# Main.net
KiCad netlist of a schematic drawn in Altium Designer
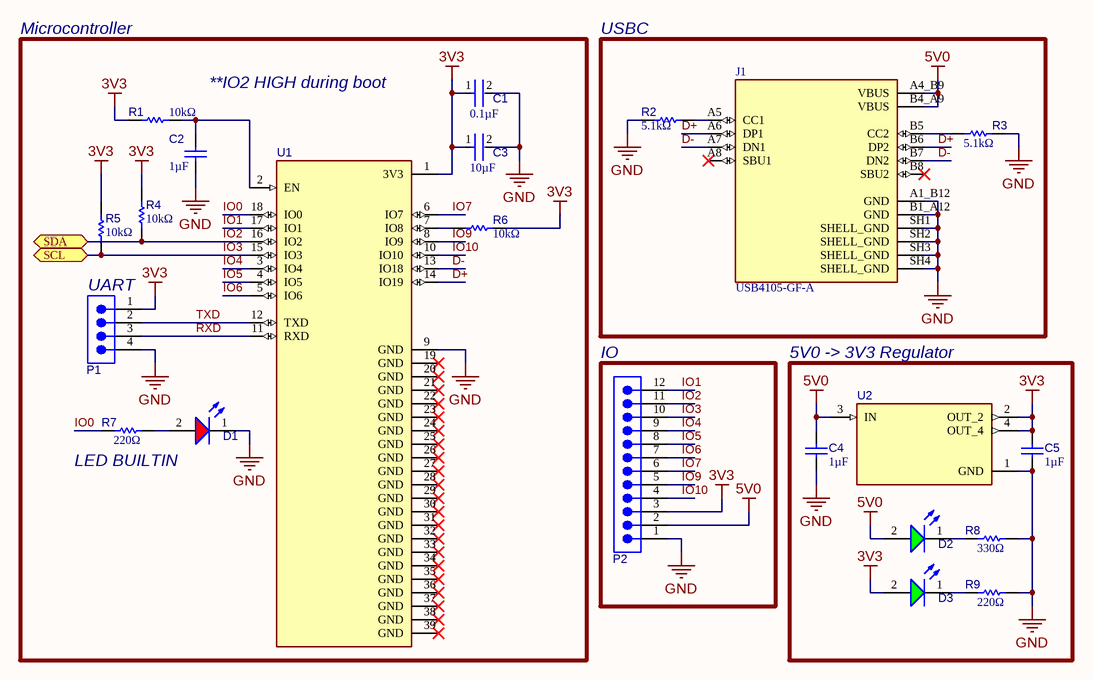
[diagram p0: Main.SchDoc]

(export (version "E")
  (design (tool "Eeschema 10.0.6"))
  (components
    (comp (ref "C1")
      (value "0.1µF")
      (footprint "FP-C1206C-EB-MFG")
      (description "CAP CER 0.1UF 100V X7R 1206")
      (fields
        (field (name "TOLERANCE") "0.1")
        (field (name "OCTOPART") "https://octopart.com/c1206c104k1ractu-kemet-89521")
      )
      (libsource (lib "Altium Content Vault") (part "b4654b650e69147ec39a6b967a45e02"))
    )
    (comp (ref "C2")
      (value "1µF")
      (footprint "CAPC3216X110X50LL20T25")
      (description "Chip Capacitor, 1 uF, +/- 10%, 50 V, -55 to 125 degC, 1206 (3216 Metric), RoHS, Tape and Reel")
      (fields (field (name "MANUFACTURER") "Kemet") (field (name "TOLERANCE") "10%"))
      (libsource (lib "Altium Content Vault") (part "CAP-NP-2"))
    )
    (comp (ref "C3")
      (value "10µF")
      (footprint "FP-GRM31C-0_2-e0_3_0_8-MFG")
      (description "Chip Multilayer Ceramic Capacitors for General Purpose, 1206, 10uF, X7R, 15%, 10%, 25V")
      (fields (field (name "TOLERANCE") "10%") (field (name "VOLTAGE") "25V"))
      (libsource (lib "Altium Content Vault") (part "02cd4be3c70576c341d710602a673aa"))
    )
    (comp (ref "C4")
      (value "1µF")
      (footprint "CAPC3216X110X50LL20T25")
      (description "Chip Capacitor, 1 uF, +/- 10%, 50 V, -55 to 125 degC, 1206 (3216 Metric), RoHS, Tape and Reel")
      (fields (field (name "MANUFACTURER") "Kemet") (field (name "TOLERANCE") "10%"))
      (libsource (lib "Altium Content Vault") (part "CAP-NP-2"))
    )
    (comp (ref "C5")
      (value "1µF")
      (footprint "CAPC3216X110X50LL20T25")
      (description "Chip Capacitor, 1 uF, +/- 10%, 50 V, -55 to 125 degC, 1206 (3216 Metric), RoHS, Tape and Reel")
      (fields (field (name "MANUFACTURER") "Kemet") (field (name "TOLERANCE") "10%"))
      (libsource (lib "Altium Content Vault") (part "CAP-NP-2"))
    )
    (comp (ref "D1")
      (value "150120SS75000")
      (footprint "WL-SMCW_1206_150120xx75000")
      (description "Led, Red, 630 Nm, 1.9 V, 30 Ma, 60 Mcd Rohs Compliant: Yes")
      (libsource (lib "Altium Content Vault") (part "LED_Red_2A-1K"))
    )
    (comp (ref "D2")
      (value "150120GS75000")
      (footprint "WL-SMCW_1206_150120xx75000")
      (description "WL-SMCW SMT Mono-Color Chip LED Waterclear")
      (libsource (lib "Altium Content Vault") (part "LED_Green_2A-1K"))
    )
    (comp (ref "D3")
      (value "150120GS75000")
      (footprint "WL-SMCW_1206_150120xx75000")
      (description "WL-SMCW SMT Mono-Color Chip LED Waterclear")
      (libsource (lib "Altium Content Vault") (part "LED_Green_2A-1K"))
    )
    (comp (ref "J1")
      (value "USB4105-GF-A")
      (footprint "GCT_USB4105-GF-A")
      (fields (field (name "MF") "{'manufacturer': u'GCT'}"))
      (libsource (lib "USB4105-GF-A") (part "USB4105-GF-A"))
    )
    (comp (ref "P1")
      (value "61300411121")
      (footprint "61300411121")
      (description "WR-PHD Pin Header, THT, Vertical, pitch 2.54mm, 1 Row, 4P")
      (fields (field (name "MANUFACTURER") "Wurth Elektronik"))
      (libsource (lib "Altium_WR-PHD_rev24a") (part "61300411121"))
    )
    (comp (ref "P2")
      (value "61301211121")
      (footprint "61301211121")
      (description "WR-PHD Pin Header, THT, Vertical, pitch 2.54mm, 1 Row, 12P")
      (fields (field (name "MANUFACTURER") "Wurth Elektronik"))
      (libsource (lib "Altium_WR-PHD_rev24a") (part "61301211121"))
    )
    (comp (ref "R1")
      (value "10kΩ")
      (footprint "RESC3216X70X50LL20T25")
      (fields (field (name "MANUFACTURER") "Panasonic") (field (name "PART NUMBER") "ERA8AEB103V"))
      (libsource (lib "Altium Content Vault") (part "RES"))
    )
    (comp (ref "R2")
      (value "5.1kΩ")
      (footprint "RESC3216X70X50NL05T20")
      (fields (field (name "PART NUMBER") "ERJ-8ENF5101V") (field (name "MANUFACTURER") "Panasonic"))
      (libsource (lib "Altium Content Vault") (part "RES"))
    )
    (comp (ref "R3")
      (value "5.1kΩ")
      (footprint "RESC3216X70X50NL05T20")
      (fields (field (name "PART NUMBER") "ERJ-8ENF5101V") (field (name "MANUFACTURER") "Panasonic"))
      (libsource (lib "Altium Content Vault") (part "RES"))
    )
    (comp (ref "R4")
      (value "10kΩ")
      (footprint "RESC3216X70X50LL20T25")
      (fields (field (name "MANUFACTURER") "Panasonic") (field (name "PART NUMBER") "ERA8AEB103V"))
      (libsource (lib "Altium Content Vault") (part "RES"))
    )
    (comp (ref "R5")
      (value "10kΩ")
      (footprint "RESC3216X70X50LL20T25")
      (fields (field (name "MANUFACTURER") "Panasonic") (field (name "PART NUMBER") "ERA8AEB103V"))
      (libsource (lib "Altium Content Vault") (part "RES"))
    )
    (comp (ref "R6")
      (value "10kΩ")
      (footprint "RESC3216X70X50LL20T25")
      (fields (field (name "MANUFACTURER") "Panasonic") (field (name "PART NUMBER") "ERA8AEB103V"))
      (libsource (lib "Altium Content Vault") (part "RES"))
    )
    (comp (ref "R7")
      (value "220Ω")
      (footprint "RESC3216X70X50ML20T25")
      (fields (field (name "PART NUMBER") "ERA8AEB221V") (field (name "MANUFACTURER") "Panasonic"))
      (libsource (lib "Altium Content Vault") (part "RES"))
    )
    (comp (ref "R8")
      (value "330Ω")
      (footprint "RESC3216X70X50NL05T20")
      (fields (field (name "MANUFACTURER") "Panasonic") (field (name "PART NUMBER") "ERJ-8GEYJ331V"))
      (libsource (lib "Altium Content Vault") (part "RES"))
    )
    (comp (ref "R9")
      (value "220Ω")
      (footprint "RESC3216X70X50ML20T25")
      (fields (field (name "PART NUMBER") "ERA8AEB221V") (field (name "MANUFACTURER") "Panasonic"))
      (libsource (lib "Altium Content Vault") (part "RES"))
    )
    (comp (ref "U1")
      (value "ESP32-C3-WROOM-02-N4")
      (footprint "MODULE_ESP32-C3-WROOM-02-H4")
      (fields (field (name "MF") "Espressif Systems"))
      (libsource (lib "ESP32-C3-WROOM-02-N4") (part "ESP32-C3-WROOM-02-N4"))
    )
    (comp (ref "U2")
      (value "TLV1117LV33DCYR")
      (footprint "VREG_TLV1117LV33DCYR")
      (description "1-A, low-dropout voltage regulator")
      (fields (field (name "DIGI-KEY_PART_NUMBER") "296-28778-2-ND") (field (name "MF") "Texas Instruments"))
      (libsource (lib "TLV1117LV33DCYR") (part "TLV1117LV33DCYR"))
    )
  )
  (nets
    (net (code "1") (name "/D+") (class "Default")
      (node (ref "J1") (pin "A6") (pinfunction "DP1_A6") (pintype "bidirectional"))
      (node (ref "J1") (pin "B6") (pinfunction "DP2_B6") (pintype "bidirectional"))
      (node (ref "U1") (pin "14") (pinfunction "IO19_14") (pintype "bidirectional"))
    )
    (net (code "2") (name "/D-") (class "Default")
      (node (ref "J1") (pin "A7") (pinfunction "DN1_A7") (pintype "bidirectional"))
      (node (ref "J1") (pin "B7") (pinfunction "DN2_B7") (pintype "bidirectional"))
      (node (ref "U1") (pin "13") (pinfunction "IO18_13") (pintype "bidirectional"))
    )
    (net (code "3") (name "/IO0") (class "Default")
      (node (ref "R7") (pin "1") (pinfunction "1_1") (pintype "passive"))
      (node (ref "U1") (pin "18") (pinfunction "IO0_18") (pintype "bidirectional"))
    )
    (net (code "4") (name "/IO1") (class "Default")
      (node (ref "P2") (pin "12") (pinfunction "12_12") (pintype "passive"))
      (node (ref "U1") (pin "17") (pinfunction "IO1_17") (pintype "bidirectional"))
    )
    (net (code "5") (name "/IO2") (class "Default")
      (node (ref "P2") (pin "11") (pinfunction "11_11") (pintype "passive"))
      (node (ref "R4") (pin "1") (pinfunction "1_1") (pintype "passive"))
      (node (ref "U1") (pin "16") (pinfunction "IO2_16") (pintype "bidirectional"))
    )
    (net (code "6") (name "/IO3") (class "Default")
      (node (ref "P2") (pin "10") (pinfunction "10_10") (pintype "passive"))
      (node (ref "R5") (pin "1") (pinfunction "1_1") (pintype "passive"))
      (node (ref "U1") (pin "15") (pinfunction "IO3_15") (pintype "bidirectional"))
    )
    (net (code "7") (name "/IO4") (class "Default")
      (node (ref "P2") (pin "9") (pinfunction "9_9") (pintype "passive"))
      (node (ref "U1") (pin "3") (pinfunction "IO4_3") (pintype "bidirectional"))
    )
    (net (code "8") (name "/IO5") (class "Default")
      (node (ref "P2") (pin "8") (pinfunction "8_8") (pintype "passive"))
      (node (ref "U1") (pin "4") (pinfunction "IO5_4") (pintype "bidirectional"))
    )
    (net (code "9") (name "/IO6") (class "Default")
      (node (ref "P2") (pin "7") (pinfunction "7_7") (pintype "passive"))
      (node (ref "U1") (pin "5") (pinfunction "IO6_5") (pintype "bidirectional"))
    )
    (net (code "10") (name "/IO7") (class "Default")
      (node (ref "P2") (pin "6") (pinfunction "6_6") (pintype "passive"))
      (node (ref "U1") (pin "6") (pinfunction "IO7_6") (pintype "bidirectional"))
    )
    (net (code "11") (name "/IO9") (class "Default")
      (node (ref "P2") (pin "5") (pinfunction "5_5") (pintype "passive"))
      (node (ref "U1") (pin "8") (pinfunction "IO9_8") (pintype "bidirectional"))
    )
    (net (code "12") (name "/IO10") (class "Default")
      (node (ref "P2") (pin "4") (pinfunction "4_4") (pintype "passive"))
      (node (ref "U1") (pin "10") (pinfunction "IO10_10") (pintype "bidirectional"))
    )
    (net (code "13") (name "/RXD") (class "Default")
      (node (ref "P1") (pin "3") (pinfunction "3_3") (pintype "passive"))
      (node (ref "U1") (pin "11") (pinfunction "RXD_11") (pintype "bidirectional"))
    )
    (net (code "14") (name "/TXD") (class "Default")
      (node (ref "P1") (pin "2") (pinfunction "2_2") (pintype "passive"))
      (node (ref "U1") (pin "12") (pinfunction "TXD_12") (pintype "bidirectional"))
    )
    (net (code "15") (name "3V3") (class "Default")
      (node (ref "C1") (pin "1") (pinfunction "1_1") (pintype "passive"))
      (node (ref "C3") (pin "1") (pinfunction "1_1") (pintype "passive"))
      (node (ref "C5") (pin "2") (pinfunction "2_2") (pintype "passive"))
      (node (ref "D3") (pin "2") (pinfunction "A_2") (pintype "passive"))
      (node (ref "P1") (pin "1") (pinfunction "1_1") (pintype "passive"))
      (node (ref "P2") (pin "3") (pinfunction "3_3") (pintype "passive"))
      (node (ref "R1") (pin "1") (pinfunction "1_1") (pintype "passive"))
      (node (ref "R4") (pin "2") (pinfunction "2_2") (pintype "passive"))
      (node (ref "R5") (pin "2") (pinfunction "2_2") (pintype "passive"))
      (node (ref "R6") (pin "2") (pinfunction "2_2") (pintype "passive"))
      (node (ref "U1") (pin "1") (pinfunction "3V3_1") (pintype "power_in"))
      (node (ref "U2") (pin "2") (pinfunction "OUT_2_2") (pintype "output"))
      (node (ref "U2") (pin "4") (pinfunction "OUT_4_4") (pintype "output"))
    )
    (net (code "16") (name "5V0") (class "Default")
      (node (ref "C4") (pin "2") (pinfunction "2_2") (pintype "passive"))
      (node (ref "D2") (pin "2") (pinfunction "A_2") (pintype "passive"))
      (node (ref "J1") (pin "A4_B9") (pinfunction "VBUS_A4_B9") (pintype "power_in"))
      (node (ref "J1") (pin "B4_A9") (pinfunction "VBUS_B4_A9") (pintype "power_in"))
      (node (ref "P2") (pin "2") (pinfunction "2_2") (pintype "passive"))
      (node (ref "U2") (pin "3") (pinfunction "IN_3") (pintype "input"))
    )
    (net (code "17") (name "GND") (class "Default")
      (node (ref "C1") (pin "2") (pinfunction "2_2") (pintype "passive"))
      (node (ref "C2") (pin "1") (pinfunction "1_1") (pintype "passive"))
      (node (ref "C3") (pin "2") (pinfunction "2_2") (pintype "passive"))
      (node (ref "C4") (pin "1") (pinfunction "1_1") (pintype "passive"))
      (node (ref "C5") (pin "1") (pinfunction "1_1") (pintype "passive"))
      (node (ref "D1") (pin "1") (pinfunction "K_1") (pintype "passive"))
      (node (ref "J1") (pin "A1_B12") (pinfunction "GND_A1_B12") (pintype "power_in"))
      (node (ref "J1") (pin "B1_A12") (pinfunction "GND_B1_A12") (pintype "power_in"))
      (node (ref "J1") (pin "SH1") (pinfunction "SHELL_GND_SH1") (pintype "power_in"))
      (node (ref "J1") (pin "SH2") (pinfunction "SHELL_GND_SH2") (pintype "power_in"))
      (node (ref "J1") (pin "SH3") (pinfunction "SHELL_GND_SH3") (pintype "power_in"))
      (node (ref "J1") (pin "SH4") (pinfunction "SHELL_GND_SH4") (pintype "power_in"))
      (node (ref "P1") (pin "4") (pinfunction "4_4") (pintype "passive"))
      (node (ref "P2") (pin "1") (pinfunction "1_1") (pintype "passive"))
      (node (ref "R2") (pin "1") (pinfunction "1_1") (pintype "passive"))
      (node (ref "R3") (pin "2") (pinfunction "2_2") (pintype "passive"))
      (node (ref "R8") (pin "2") (pinfunction "2_2") (pintype "passive"))
      (node (ref "R9") (pin "2") (pinfunction "2_2") (pintype "passive"))
      (node (ref "U1") (pin "9") (pinfunction "GND_9") (pintype "power_in"))
      (node (ref "U2") (pin "1") (pinfunction "GND_1") (pintype "power_in"))
    )
    (net (code "18") (name "Net-(D1-A)") (class "Default")
      (node (ref "D1") (pin "2") (pinfunction "A_2") (pintype "passive"))
      (node (ref "R7") (pin "2") (pinfunction "2_2") (pintype "passive"))
    )
    (net (code "19") (name "Net-(D2-K)") (class "Default")
      (node (ref "D2") (pin "1") (pinfunction "K_1") (pintype "passive"))
      (node (ref "R8") (pin "1") (pinfunction "1_1") (pintype "passive"))
    )
    (net (code "20") (name "Net-(D3-K)") (class "Default")
      (node (ref "D3") (pin "1") (pinfunction "K_1") (pintype "passive"))
      (node (ref "R9") (pin "1") (pinfunction "1_1") (pintype "passive"))
    )
    (net (code "21") (name "Net-(J1-CC1)") (class "Default")
      (node (ref "J1") (pin "A5") (pinfunction "CC1_A5") (pintype "bidirectional"))
      (node (ref "R2") (pin "2") (pinfunction "2_2") (pintype "passive"))
    )
    (net (code "22") (name "Net-(J1-CC2)") (class "Default")
      (node (ref "J1") (pin "B5") (pinfunction "CC2_B5") (pintype "bidirectional"))
      (node (ref "R3") (pin "1") (pinfunction "1_1") (pintype "passive"))
    )
    (net (code "23") (name "Net-(U1-EN)") (class "Default")
      (node (ref "C2") (pin "2") (pinfunction "2_2") (pintype "passive"))
      (node (ref "R1") (pin "2") (pinfunction "2_2") (pintype "passive"))
      (node (ref "U1") (pin "2") (pinfunction "EN_2") (pintype "input"))
    )
    (net (code "24") (name "Net-(U1-IO8)") (class "Default")
      (node (ref "R6") (pin "1") (pinfunction "1_1") (pintype "passive"))
      (node (ref "U1") (pin "7") (pinfunction "IO8_7") (pintype "bidirectional"))
    )
    (net (code "25") (name "unconnected-(J1-SBU1-PadA8)") (class "Default")
      (node (ref "J1") (pin "A8") (pinfunction "SBU1_A8") (pintype "bidirectional+no_connect"))
    )
    (net (code "26") (name "unconnected-(J1-SBU2-PadB8)") (class "Default")
      (node (ref "J1") (pin "B8") (pinfunction "SBU2_B8") (pintype "bidirectional+no_connect"))
    )
    (net (code "27") (name "unconnected-(U1-GND-Pad19)") (class "Default")
      (node (ref "U1") (pin "19") (pinfunction "GND_19") (pintype "power_in+no_connect"))
    )
    (net (code "28") (name "unconnected-(U1-GND-Pad20)") (class "Default")
      (node (ref "U1") (pin "20") (pinfunction "GND_20") (pintype "power_in+no_connect"))
    )
    (net (code "29") (name "unconnected-(U1-GND-Pad21)") (class "Default")
      (node (ref "U1") (pin "21") (pinfunction "GND_21") (pintype "power_in+no_connect"))
    )
    (net (code "30") (name "unconnected-(U1-GND-Pad22)") (class "Default")
      (node (ref "U1") (pin "22") (pinfunction "GND_22") (pintype "power_in+no_connect"))
    )
    (net (code "31") (name "unconnected-(U1-GND-Pad23)") (class "Default")
      (node (ref "U1") (pin "23") (pinfunction "GND_23") (pintype "power_in+no_connect"))
    )
    (net (code "32") (name "unconnected-(U1-GND-Pad24)") (class "Default")
      (node (ref "U1") (pin "24") (pinfunction "GND_24") (pintype "power_in+no_connect"))
    )
    (net (code "33") (name "unconnected-(U1-GND-Pad25)") (class "Default")
      (node (ref "U1") (pin "25") (pinfunction "GND_25") (pintype "power_in+no_connect"))
    )
    (net (code "34") (name "unconnected-(U1-GND-Pad26)") (class "Default")
      (node (ref "U1") (pin "26") (pinfunction "GND_26") (pintype "power_in+no_connect"))
    )
    (net (code "35") (name "unconnected-(U1-GND-Pad27)") (class "Default")
      (node (ref "U1") (pin "27") (pinfunction "GND_27") (pintype "power_in+no_connect"))
    )
    (net (code "36") (name "unconnected-(U1-GND-Pad28)") (class "Default")
      (node (ref "U1") (pin "28") (pinfunction "GND_28") (pintype "power_in+no_connect"))
    )
    (net (code "37") (name "unconnected-(U1-GND-Pad29)") (class "Default")
      (node (ref "U1") (pin "29") (pinfunction "GND_29") (pintype "power_in+no_connect"))
    )
    (net (code "38") (name "unconnected-(U1-GND-Pad30)") (class "Default")
      (node (ref "U1") (pin "30") (pinfunction "GND_30") (pintype "power_in+no_connect"))
    )
    (net (code "39") (name "unconnected-(U1-GND-Pad31)") (class "Default")
      (node (ref "U1") (pin "31") (pinfunction "GND_31") (pintype "power_in+no_connect"))
    )
    (net (code "40") (name "unconnected-(U1-GND-Pad32)") (class "Default")
      (node (ref "U1") (pin "32") (pinfunction "GND_32") (pintype "power_in+no_connect"))
    )
    (net (code "41") (name "unconnected-(U1-GND-Pad33)") (class "Default")
      (node (ref "U1") (pin "33") (pinfunction "GND_33") (pintype "power_in+no_connect"))
    )
    (net (code "42") (name "unconnected-(U1-GND-Pad34)") (class "Default")
      (node (ref "U1") (pin "34") (pinfunction "GND_34") (pintype "power_in+no_connect"))
    )
    (net (code "43") (name "unconnected-(U1-GND-Pad35)") (class "Default")
      (node (ref "U1") (pin "35") (pinfunction "GND_35") (pintype "power_in+no_connect"))
    )
    (net (code "44") (name "unconnected-(U1-GND-Pad36)") (class "Default")
      (node (ref "U1") (pin "36") (pinfunction "GND_36") (pintype "power_in+no_connect"))
    )
    (net (code "45") (name "unconnected-(U1-GND-Pad37)") (class "Default")
      (node (ref "U1") (pin "37") (pinfunction "GND_37") (pintype "power_in+no_connect"))
    )
    (net (code "46") (name "unconnected-(U1-GND-Pad38)") (class "Default")
      (node (ref "U1") (pin "38") (pinfunction "GND_38") (pintype "power_in+no_connect"))
    )
    (net (code "47") (name "unconnected-(U1-GND-Pad39)") (class "Default")
      (node (ref "U1") (pin "39") (pinfunction "GND_39") (pintype "power_in+no_connect"))
    )
  )
)
